# attinier85-motherboard-mk-1_0.net
KiCad netlist of a schematic drawn in EAGLE
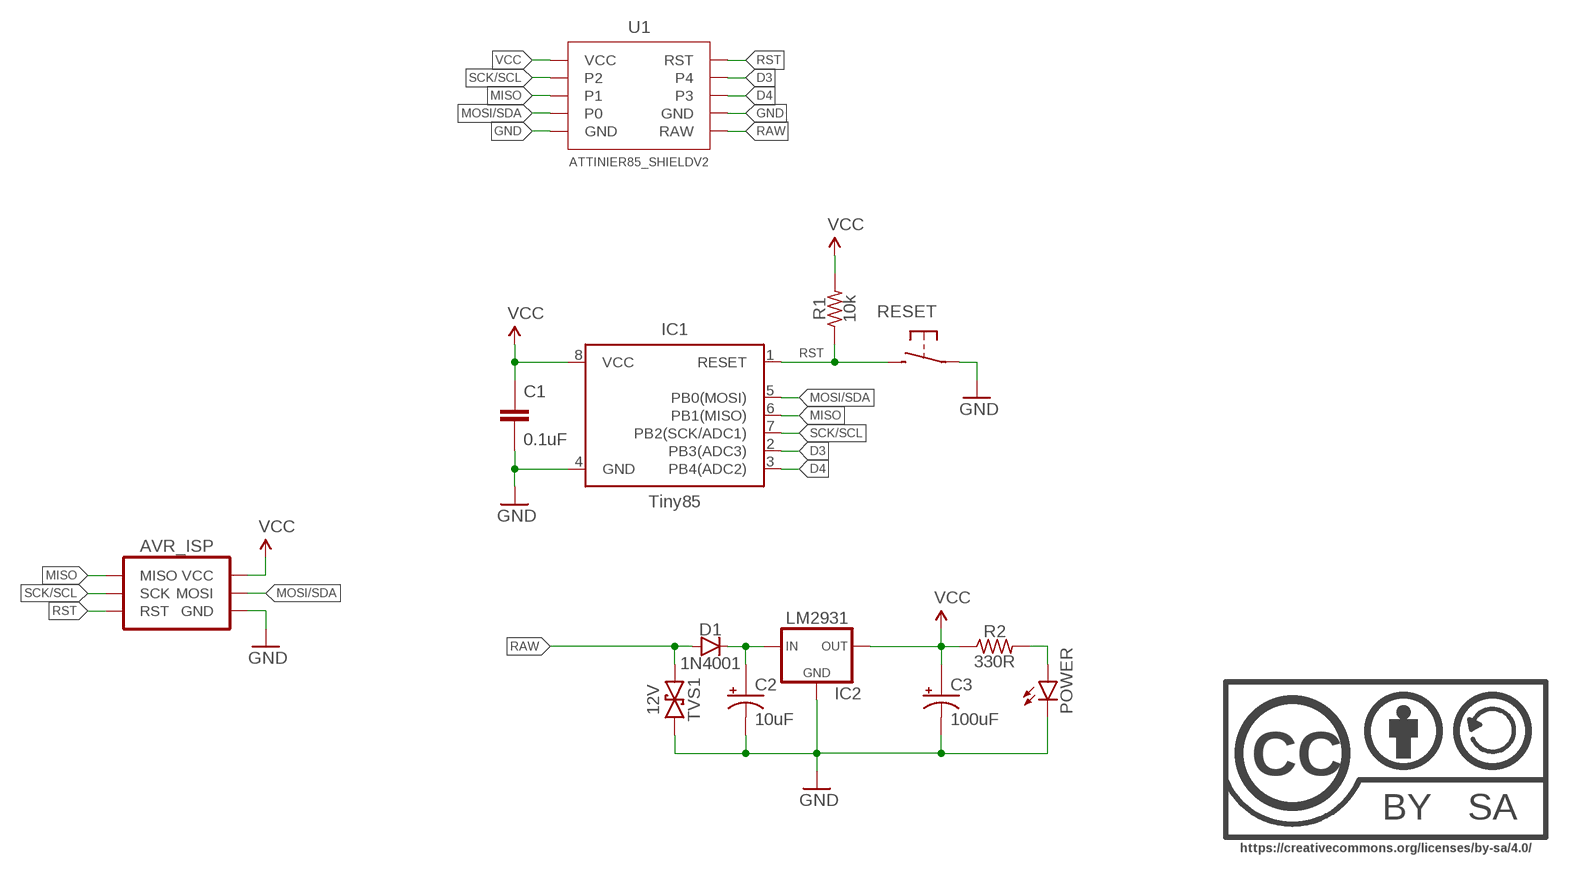
[diagram p0: schematic, sheet 1]

(export (version "E")
  (design (tool "Eeschema 10.0.6"))
  (components
    (comp (ref "AVR_ISP")
      (value "AVR_SPI_PRG_6PTH")
      (footprint "eagle-import:2X3")
      (libsource (lib "eagle-import") (part "AVR_SPI_PRG_6PTH"))
    )
    (comp (ref "C1")
      (value "0.1uF")
      (footprint "eagle-import:C025-024X044")
      (libsource (lib "eagle-import") (part "CAPACITOR-CERAMIC025-024X044"))
    )
    (comp (ref "C2")
      (value "10uF")
      (footprint "eagle-import:E2,5-5")
      (libsource (lib "eagle-import") (part "CAPACITOR-POLARIZEDE2.5-5"))
    )
    (comp (ref "C3")
      (value "100uF")
      (footprint "eagle-import:E2,5-5")
      (libsource (lib "eagle-import") (part "CAPACITOR-POLARIZEDE2.5-5"))
    )
    (comp (ref "D1")
      (value "1N4001")
      (footprint "eagle-import:DIODE-10.16MM")
      (libsource (lib "eagle-import") (part "DIODEPTH-10.68MM"))
    )
    (comp (ref "IC1")
      (value "Tiny85")
      (footprint "eagle-import:DIP08")
      (libsource (lib "eagle-import") (part "ATTINY45TINY85-20-DIP"))
    )
    (comp (ref "IC2")
      (value "LM2931")
      (footprint "eagle-import:TO-92-AMMO")
      (libsource (lib "eagle-import") (part "V_REG_78XXTO-92-INLINE"))
    )
    (comp (ref "POWER")
      (value "LED3MM-LESS")
      (footprint "eagle-import:LED3MM-LESSSILK")
      (libsource (lib "eagle-import") (part "LED3MM-LESS"))
    )
    (comp (ref "R1")
      (value "10k")
      (footprint "eagle-import:RESISTOR-AXIAL-PTH-7.62MM")
      (libsource (lib "eagle-import") (part "RESISTORPTH-AXIAL-7.62MM"))
    )
    (comp (ref "R2")
      (value "330R")
      (footprint "eagle-import:RESISTOR-AXIAL-PTH-7.62MM")
      (libsource (lib "eagle-import") (part "RESISTORPTH-AXIAL-7.62MM"))
    )
    (comp (ref "RESET")
      (value "DTS-6MM")
      (footprint "eagle-import:DTS-3-SMALL-PADS")
      (libsource (lib "eagle-import") (part "SPST-NO-TACT3MM-PTH-SMALL-PADS"))
    )
    (comp (ref "TVS1")
      (value "12V")
      (footprint "eagle-import:DO-41-TVS")
      (libsource (lib "eagle-import") (part "TVSDO-41-TVS-BIDIRECTIONAL"))
    )
    (comp (ref "U$1")
      (value "CC-BY-SA-4.0NO-URL")
      (footprint "eagle-import:CC-BY-SA-4.0-NO-URL")
      (libsource (lib "eagle-import") (part "CC-BY-SA-4.0NO-URL"))
    )
    (comp (ref "U1")
      (value "ATTINIER85_SHIELDV2")
      (footprint "eagle-import:ATTINIER85_SHIELD_V2")
      (libsource (lib "eagle-import") (part "ATTINIER85_SHIELDV2"))
    )
  )
  (nets
    (net (code "1") (name "D3") (class "Default")
      (node (ref "IC1") (pin "2") (pinfunction "PB3(ADC3)_2") (pintype "bidirectional"))
      (node (ref "U1") (pin "4") (pinfunction "P4_4") (pintype "bidirectional"))
    )
    (net (code "2") (name "D4") (class "Default")
      (node (ref "IC1") (pin "3") (pinfunction "PB4(ADC2)_3") (pintype "bidirectional"))
      (node (ref "U1") (pin "3") (pinfunction "P3_3") (pintype "bidirectional"))
    )
    (net (code "3") (name "GND") (class "Default")
      (node (ref "AVR_ISP") (pin "6") (pinfunction "GND_6") (pintype "passive"))
      (node (ref "C1") (pin "2") (pinfunction "2_2") (pintype "passive"))
      (node (ref "C2") (pin "-") (pinfunction "-_-") (pintype "passive"))
      (node (ref "C3") (pin "-") (pinfunction "-_-") (pintype "passive"))
      (node (ref "IC1") (pin "4") (pinfunction "GND_4") (pintype "bidirectional"))
      (node (ref "IC2") (pin "2") (pinfunction "GND_2") (pintype "bidirectional"))
      (node (ref "POWER") (pin "K") (pinfunction "C_K") (pintype "passive"))
      (node (ref "RESET") (pin "1") (pinfunction "1_1") (pintype "passive"))
      (node (ref "TVS1") (pin "P$2") (pinfunction "2_P$2") (pintype "passive"))
      (node (ref "U1") (pin "GND@1") (pinfunction "GND_GND@1") (pintype "bidirectional"))
      (node (ref "U1") (pin "GND@2") (pinfunction "GND_GND@2") (pintype "bidirectional"))
    )
    (net (code "4") (name "MISO") (class "Default")
      (node (ref "AVR_ISP") (pin "1") (pinfunction "MISO_1") (pintype "passive"))
      (node (ref "IC1") (pin "6") (pinfunction "PB1(MISO)_6") (pintype "bidirectional"))
      (node (ref "U1") (pin "1") (pinfunction "P1_1") (pintype "bidirectional"))
    )
    (net (code "5") (name "MOSI{slash}SDA") (class "Default")
      (node (ref "AVR_ISP") (pin "4") (pinfunction "MOSI_4") (pintype "passive"))
      (node (ref "IC1") (pin "5") (pinfunction "PB0(MOSI)_5") (pintype "bidirectional"))
      (node (ref "U1") (pin "0") (pinfunction "P0_0") (pintype "bidirectional"))
    )
    (net (code "6") (name "Net-(IC2-IN)") (class "Default")
      (node (ref "C2") (pin "+") (pinfunction "+_+") (pintype "passive"))
      (node (ref "D1") (pin "C") (pinfunction "C_C") (pintype "passive"))
      (node (ref "IC2") (pin "1") (pinfunction "IN_1") (pintype "bidirectional"))
    )
    (net (code "7") (name "Net-(R2-2)") (class "Default")
      (node (ref "POWER") (pin "A") (pinfunction "A_A") (pintype "passive"))
      (node (ref "R2") (pin "P$2") (pinfunction "2_P$2") (pintype "passive"))
    )
    (net (code "8") (name "RAW") (class "Default")
      (node (ref "D1") (pin "A") (pinfunction "A_A") (pintype "passive"))
      (node (ref "TVS1") (pin "P$1") (pinfunction "1_P$1") (pintype "passive"))
      (node (ref "U1") (pin "RAW") (pinfunction "RAW_RAW") (pintype "bidirectional"))
    )
    (net (code "9") (name "RST") (class "Default")
      (node (ref "AVR_ISP") (pin "5") (pinfunction "RST_5") (pintype "passive"))
      (node (ref "IC1") (pin "1") (pinfunction "RESET_1") (pintype "bidirectional"))
      (node (ref "R1") (pin "P$1") (pinfunction "1_P$1") (pintype "passive"))
      (node (ref "RESET") (pin "2") (pinfunction "2_2") (pintype "passive"))
      (node (ref "U1") (pin "RST") (pinfunction "RST_RST") (pintype "bidirectional"))
    )
    (net (code "10") (name "SCK{slash}SCL") (class "Default")
      (node (ref "AVR_ISP") (pin "3") (pinfunction "SCK_3") (pintype "passive"))
      (node (ref "IC1") (pin "7") (pinfunction "PB2(SCK/ADC1)_7") (pintype "bidirectional"))
      (node (ref "U1") (pin "2") (pinfunction "P2_2") (pintype "bidirectional"))
    )
    (net (code "11") (name "VCC") (class "Default")
      (node (ref "AVR_ISP") (pin "2") (pinfunction "VCC_2") (pintype "passive"))
      (node (ref "C1") (pin "1") (pinfunction "1_1") (pintype "passive"))
      (node (ref "C3") (pin "+") (pinfunction "+_+") (pintype "passive"))
      (node (ref "IC1") (pin "8") (pinfunction "VCC_8") (pintype "bidirectional"))
      (node (ref "IC2") (pin "3") (pinfunction "OUT_3") (pintype "bidirectional"))
      (node (ref "R1") (pin "P$2") (pinfunction "2_P$2") (pintype "passive"))
      (node (ref "R2") (pin "P$1") (pinfunction "1_P$1") (pintype "passive"))
      (node (ref "U1") (pin "VCC") (pinfunction "VCC_VCC") (pintype "bidirectional"))
    )
  )
)
